# LCD.net
KiCad netlist of a schematic drawn in Altium Designer
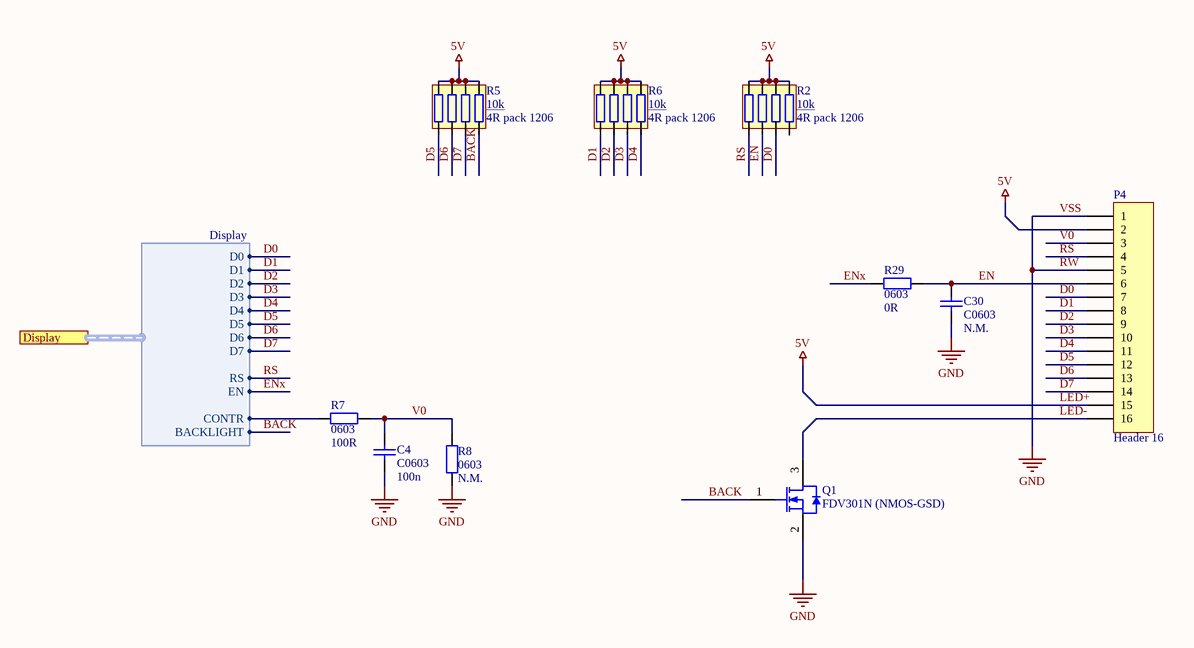
[diagram p0: LCD.SchDoc]

(export (version "E")
  (design (tool "Eeschema 10.0.6"))
  (components
    (comp (ref "C4")
      (value "100n")
      (footprint "C0603")
      (description "Generic capacitor")
      (libsource (lib "_RLC") (part "Cap"))
    )
    (comp (ref "C30")
      (value "N.M.")
      (footprint "C0603")
      (description "Generic capacitor")
      (libsource (lib "_RLC") (part "Cap"))
    )
    (comp (ref "P4")
      (value "Header 16")
      (footprint "HEADER 1X16 Female")
      (description "Header, 16-Pin")
      (fields (field (name "PUBLISHER") "Altium Limited"))
      (libsource (lib "_Connectors") (part "Header 16"))
    )
    (comp (ref "Q1")
      (value "FDV301N (NMOS-GSD)")
      (footprint "_Transistors:SOT-23_M")
      (libsource (lib "fet-n-channel") (part "NMOS-GSD"))
    )
    (comp (ref "R2")
      (value "10k")
      (footprint "4R pack 1206")
      (description "4 resistor pack array")
      (libsource (lib "_RLC") (part "Rres_pack_4"))
    )
    (comp (ref "R5")
      (value "10k")
      (footprint "4R pack 1206")
      (description "4 resistor pack array")
      (libsource (lib "_RLC") (part "Rres_pack_4"))
    )
    (comp (ref "R6")
      (value "10k")
      (footprint "4R pack 1206")
      (description "4 resistor pack array")
      (libsource (lib "_RLC") (part "Rres_pack_4"))
    )
    (comp (ref "R7")
      (value "100R")
      (footprint "0603")
      (description "Generic resistor")
      (libsource (lib "_RLC") (part "Res"))
    )
    (comp (ref "R8")
      (value "N.M.")
      (footprint "0603")
      (description "Generic resistor")
      (libsource (lib "") (part "Res_1"))
    )
    (comp (ref "R29")
      (value "0R")
      (footprint "0603")
      (description "Generic resistor")
      (libsource (lib "_RLC") (part "Res"))
    )
  )
  (nets
    (net (code "2") (name "/BACK") (class "Default")
      (node (ref "Q1") (pin "1") (pinfunction "G_1") (pintype "passive"))
      (node (ref "R5") (pin "4") (pinfunction "4_4") (pintype "passive"))
    )
    (net (code "3") (name "/CONTR") (class "Default")
      (node (ref "R7") (pin "1") (pinfunction "1_1") (pintype "passive"))
    )
    (net (code "4") (name "/D0") (class "Default")
      (node (ref "P4") (pin "7") (pinfunction "7_7") (pintype "passive"))
      (node (ref "R2") (pin "3") (pinfunction "3_3") (pintype "passive"))
    )
    (net (code "5") (name "/D1") (class "Default")
      (node (ref "P4") (pin "8") (pinfunction "8_8") (pintype "passive"))
      (node (ref "R6") (pin "1") (pinfunction "1_1") (pintype "passive"))
    )
    (net (code "6") (name "/D2") (class "Default")
      (node (ref "P4") (pin "9") (pinfunction "9_9") (pintype "passive"))
      (node (ref "R6") (pin "2") (pinfunction "2_2") (pintype "passive"))
    )
    (net (code "7") (name "/D3") (class "Default")
      (node (ref "P4") (pin "10") (pinfunction "10_10") (pintype "passive"))
      (node (ref "R6") (pin "3") (pinfunction "3_3") (pintype "passive"))
    )
    (net (code "8") (name "/D4") (class "Default")
      (node (ref "P4") (pin "11") (pinfunction "11_11") (pintype "passive"))
      (node (ref "R6") (pin "4") (pinfunction "4_4") (pintype "passive"))
    )
    (net (code "9") (name "/D5") (class "Default")
      (node (ref "P4") (pin "12") (pinfunction "12_12") (pintype "passive"))
      (node (ref "R5") (pin "1") (pinfunction "1_1") (pintype "passive"))
    )
    (net (code "10") (name "/D6") (class "Default")
      (node (ref "P4") (pin "13") (pinfunction "13_13") (pintype "passive"))
      (node (ref "R5") (pin "2") (pinfunction "2_2") (pintype "passive"))
    )
    (net (code "11") (name "/D7") (class "Default")
      (node (ref "P4") (pin "14") (pinfunction "14_14") (pintype "passive"))
      (node (ref "R5") (pin "3") (pinfunction "3_3") (pintype "passive"))
    )
    (net (code "12") (name "/EN") (class "Default")
      (node (ref "C30") (pin "1") (pinfunction "1_1") (pintype "passive"))
      (node (ref "P4") (pin "6") (pinfunction "6_6") (pintype "passive"))
      (node (ref "R2") (pin "2") (pinfunction "2_2") (pintype "passive"))
      (node (ref "R29") (pin "2") (pinfunction "2_2") (pintype "passive"))
    )
    (net (code "13") (name "/ENx") (class "Default")
      (node (ref "R29") (pin "1") (pinfunction "1_1") (pintype "passive"))
    )
    (net (code "14") (name "/LED-") (class "Default")
      (node (ref "P4") (pin "16") (pinfunction "16_16") (pintype "passive"))
      (node (ref "Q1") (pin "3") (pinfunction "D_3") (pintype "passive"))
    )
    (net (code "15") (name "/RS") (class "Default")
      (node (ref "P4") (pin "4") (pinfunction "4_4") (pintype "passive"))
      (node (ref "R2") (pin "1") (pinfunction "1_1") (pintype "passive"))
    )
    (net (code "16") (name "/V0") (class "Default")
      (node (ref "C4") (pin "1") (pinfunction "1_1") (pintype "passive"))
      (node (ref "P4") (pin "3") (pinfunction "3_3") (pintype "passive"))
      (node (ref "R7") (pin "2") (pinfunction "2_2") (pintype "passive"))
      (node (ref "R8") (pin "1") (pinfunction "1_1") (pintype "passive"))
    )
    (net (code "18") (name "5V") (class "Default")
      (node (ref "P4") (pin "15") (pinfunction "15_15") (pintype "passive"))
      (node (ref "P4") (pin "2") (pinfunction "2_2") (pintype "passive"))
      (node (ref "R2") (pin "5") (pinfunction "5_5") (pintype "passive"))
      (node (ref "R2") (pin "6") (pinfunction "6_6") (pintype "passive"))
      (node (ref "R2") (pin "7") (pinfunction "7_7") (pintype "passive"))
      (node (ref "R2") (pin "8") (pinfunction "8_8") (pintype "passive"))
      (node (ref "R5") (pin "5") (pinfunction "5_5") (pintype "passive"))
      (node (ref "R5") (pin "6") (pinfunction "6_6") (pintype "passive"))
      (node (ref "R5") (pin "7") (pinfunction "7_7") (pintype "passive"))
      (node (ref "R5") (pin "8") (pinfunction "8_8") (pintype "passive"))
      (node (ref "R6") (pin "5") (pinfunction "5_5") (pintype "passive"))
      (node (ref "R6") (pin "6") (pinfunction "6_6") (pintype "passive"))
      (node (ref "R6") (pin "7") (pinfunction "7_7") (pintype "passive"))
      (node (ref "R6") (pin "8") (pinfunction "8_8") (pintype "passive"))
    )
    (net (code "19") (name "GND") (class "Default")
      (node (ref "C30") (pin "2") (pinfunction "2_2") (pintype "passive"))
      (node (ref "C4") (pin "2") (pinfunction "2_2") (pintype "passive"))
      (node (ref "P4") (pin "1") (pinfunction "1_1") (pintype "passive"))
      (node (ref "P4") (pin "5") (pinfunction "5_5") (pintype "passive"))
      (node (ref "Q1") (pin "2") (pinfunction "S_2") (pintype "passive"))
      (node (ref "R8") (pin "2") (pinfunction "2_2") (pintype "passive"))
    )
    (net (code "20") (name "unconnected-(R2-Pad4)") (class "Default")
      (node (ref "R2") (pin "4") (pinfunction "4_4") (pintype "passive"))
    )
  )
)
